# ArduinoGardener_1_0.net
KiCad netlist of a schematic drawn in EAGLE
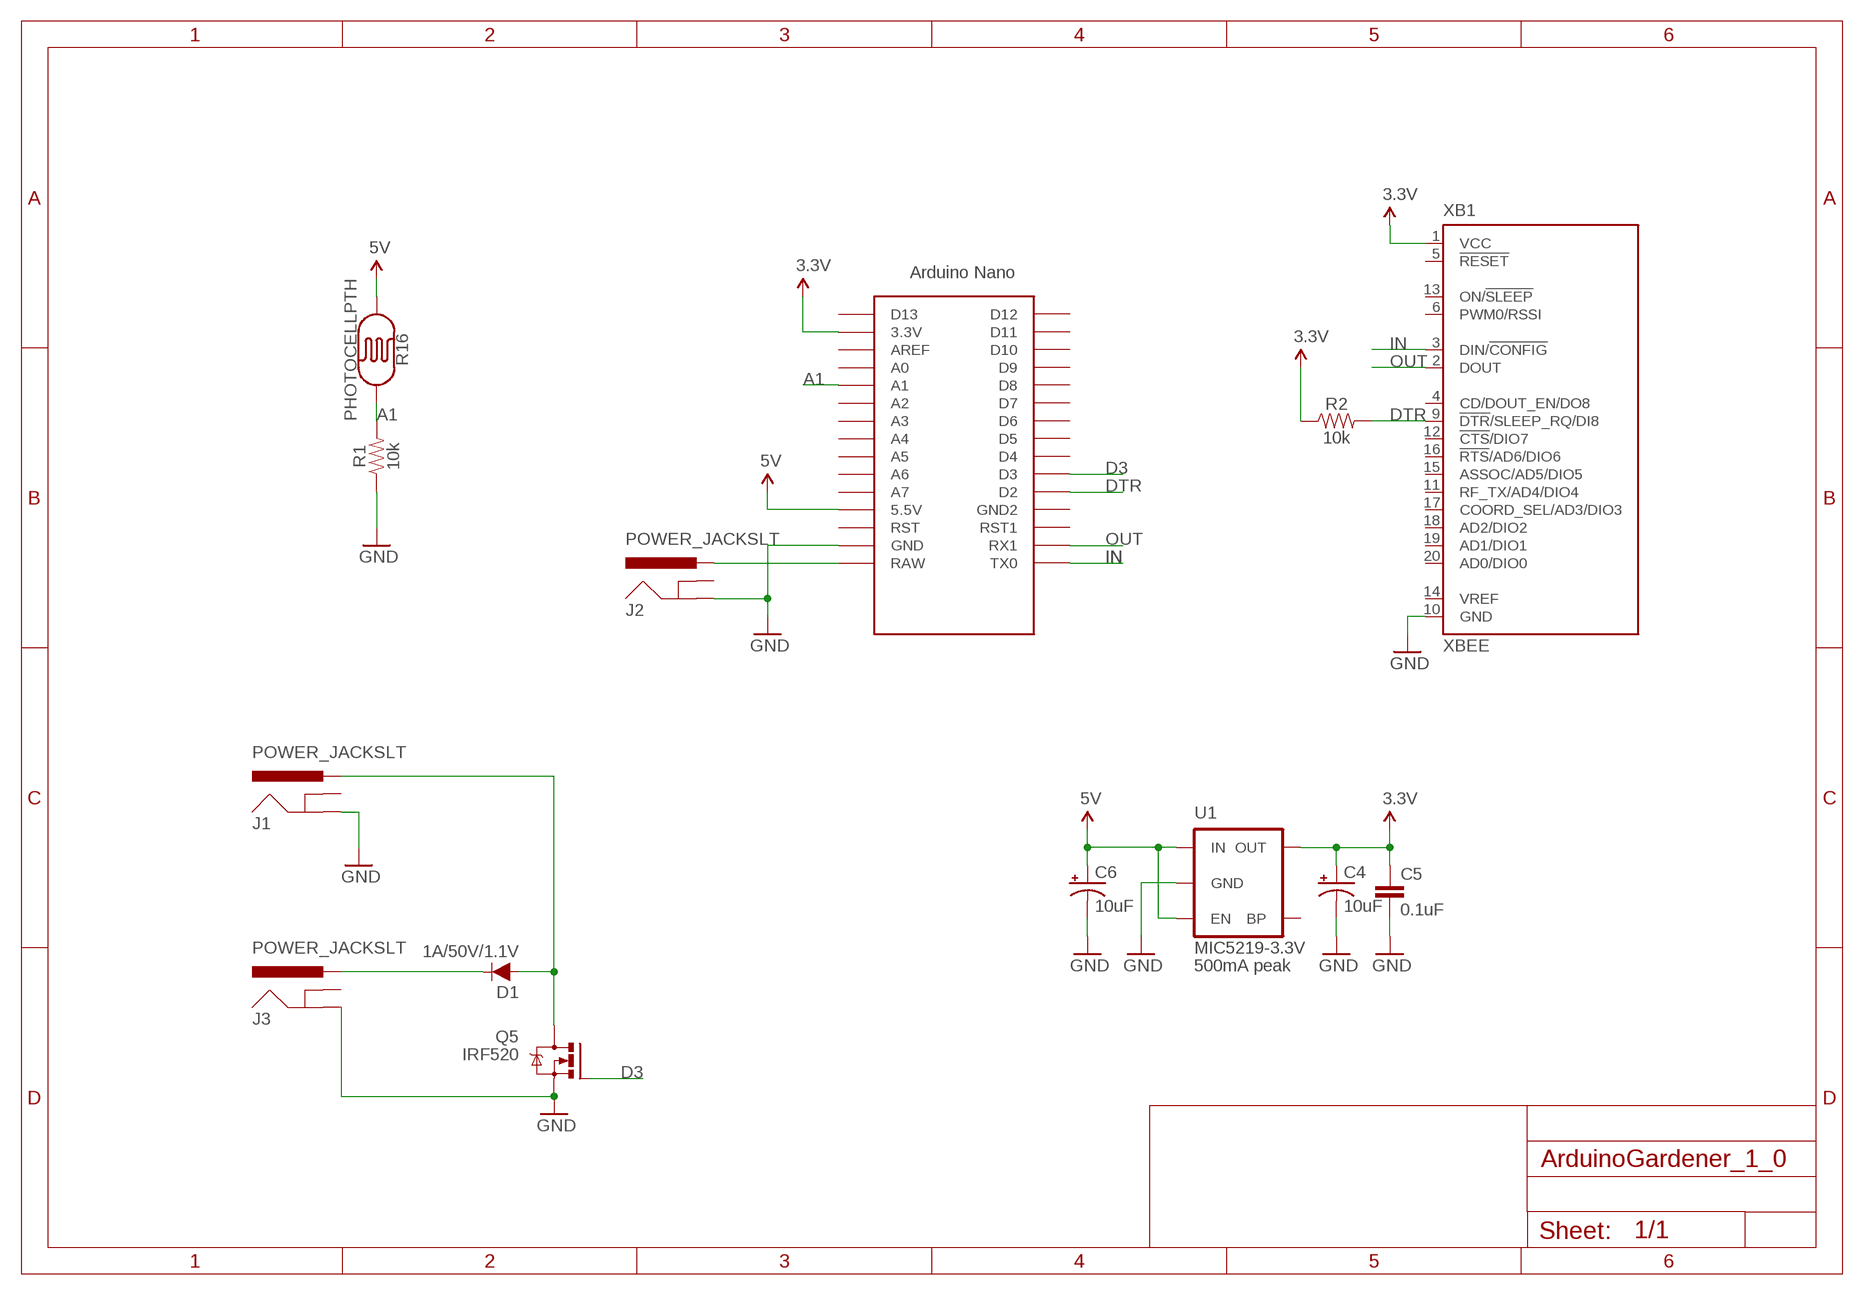
[diagram p0: schematic, sheet 1]

(export (version "E")
  (design (tool "Eeschema 10.0.6"))
  (components
    (comp (ref "C4")
      (value "10uF")
      (footprint "eagle-import:EIA3216")
      (libsource (lib "eagle-import") (part "CAP_POL1206"))
    )
    (comp (ref "C5")
      (value "0.1uF")
      (footprint "eagle-import:0402-CAP")
      (libsource (lib "eagle-import") (part "CAP0402-CAP"))
    )
    (comp (ref "C6")
      (value "10uF")
      (footprint "eagle-import:EIA3216")
      (libsource (lib "eagle-import") (part "CAP_POL1206"))
    )
    (comp (ref "D1")
      (value "1A/50V/1.1V")
      (footprint "eagle-import:DIODE-1N4001")
      (libsource (lib "eagle-import") (part "DIODE-PTH"))
    )
    (comp (ref "J1")
      (value "POWER_JACKSLT")
      (footprint "eagle-import:POWER_JACK_SLOT")
      (libsource (lib "eagle-import") (part "POWER_JACKSLT"))
    )
    (comp (ref "J2")
      (value "POWER_JACKSLT")
      (footprint "eagle-import:POWER_JACK_SLOT")
      (libsource (lib "eagle-import") (part "POWER_JACKSLT"))
    )
    (comp (ref "J3")
      (value "POWER_JACKSLT")
      (footprint "eagle-import:POWER_JACK_SLOT")
      (libsource (lib "eagle-import") (part "POWER_JACKSLT"))
    )
    (comp (ref "Q5")
      (value "IRF520")
      (footprint "eagle-import:TO220BV")
      (libsource (lib "eagle-import") (part "IRF520"))
    )
    (comp (ref "R1")
      (value "10k")
      (footprint "eagle-import:AXIAL-0.3")
      (libsource (lib "eagle-import") (part "10KOHM-HORIZ-1/4W-5%"))
    )
    (comp (ref "R2")
      (value "10k")
      (footprint "eagle-import:AXIAL-0.3")
      (libsource (lib "eagle-import") (part "10KOHM-HORIZ-1/4W-5%"))
    )
    (comp (ref "R16")
      (value "PHOTOCELLPTH")
      (footprint "eagle-import:PHOTOCELL")
      (libsource (lib "eagle-import") (part "PHOTOCELLPTH"))
    )
    (comp (ref "U$1")
      (value "NANO")
      (footprint "eagle-import:NANO")
      (libsource (lib "eagle-import") (part "NANO"))
    )
    (comp (ref "U1")
      (value "V_REG_LDOSMD")
      (footprint "eagle-import:SOT23-5")
      (libsource (lib "eagle-import") (part "V_REG_LDOSMD"))
    )
    (comp (ref "XB1")
      (value "XBEE")
      (footprint "eagle-import:XBEE")
      (fields (field (name "MPN") "XBP24-Z7UIT-004"))
      (libsource (lib "eagle-import") (part "XBEE"))
    )
  )
  (nets
    (net (code "1") (name "/A1") (class "Default")
      (node (ref "R1") (pin "P$2") (pinfunction "2_P$2") (pintype "passive"))
      (node (ref "R16") (pin "2") (pinfunction "P$2_2") (pintype "bidirectional"))
      (node (ref "U$1") (pin "A1") (pinfunction "A1_A1") (pintype "bidirectional"))
    )
    (net (code "2") (name "/D3") (class "Default")
      (node (ref "Q5") (pin "G") (pinfunction "G_G") (pintype "passive"))
      (node (ref "U$1") (pin "D3") (pinfunction "D3_D3") (pintype "bidirectional"))
    )
    (net (code "3") (name "/DTR") (class "Default")
      (node (ref "R2") (pin "P$2") (pinfunction "2_P$2") (pintype "passive"))
      (node (ref "U$1") (pin "D2") (pinfunction "D2_D2") (pintype "bidirectional"))
      (node (ref "XB1") (pin "9") (pinfunction "~{DTR}/SLEEP_RQ/DI8_9") (pintype "bidirectional"))
    )
    (net (code "4") (name "/IN") (class "Default")
      (node (ref "U$1") (pin "TX0") (pinfunction "TX0_TX0") (pintype "bidirectional"))
      (node (ref "XB1") (pin "3") (pinfunction "DIN/~{CONFIG}_3") (pintype "input"))
    )
    (net (code "5") (name "/OUT") (class "Default")
      (node (ref "U$1") (pin "RX1") (pinfunction "RX1_RX1") (pintype "bidirectional"))
      (node (ref "XB1") (pin "2") (pinfunction "DOUT_2") (pintype "output"))
    )
    (net (code "6") (name "3.3V") (class "Default")
      (node (ref "C4") (pin "A") (pinfunction "+_A") (pintype "passive"))
      (node (ref "C5") (pin "1") (pinfunction "1_1") (pintype "passive"))
      (node (ref "R2") (pin "P$1") (pinfunction "1_P$1") (pintype "passive"))
      (node (ref "U$1") (pin "3.3V") (pinfunction "3.3V_3.3V") (pintype "bidirectional"))
      (node (ref "U1") (pin "5") (pinfunction "OUT_5") (pintype "passive"))
      (node (ref "XB1") (pin "1") (pinfunction "VCC_1") (pintype "power_in"))
    )
    (net (code "7") (name "5V") (class "Default")
      (node (ref "C6") (pin "A") (pinfunction "+_A") (pintype "passive"))
      (node (ref "R16") (pin "1") (pinfunction "P$1_1") (pintype "bidirectional"))
      (node (ref "U$1") (pin "5V") (pinfunction "5.5V_5V") (pintype "bidirectional"))
      (node (ref "U1") (pin "1") (pinfunction "IN_1") (pintype "input"))
      (node (ref "U1") (pin "3") (pinfunction "EN_3") (pintype "input"))
    )
    (net (code "8") (name "GND") (class "Default")
      (node (ref "C4") (pin "C") (pinfunction "-_C") (pintype "passive"))
      (node (ref "C5") (pin "2") (pinfunction "2_2") (pintype "passive"))
      (node (ref "C6") (pin "C") (pinfunction "-_C") (pintype "passive"))
      (node (ref "J1") (pin "GND@2") (pinfunction "GND_GND@2") (pintype "bidirectional"))
      (node (ref "J2") (pin "GND@2") (pinfunction "GND_GND@2") (pintype "bidirectional"))
      (node (ref "J3") (pin "GND@2") (pinfunction "GND_GND@2") (pintype "bidirectional"))
      (node (ref "Q5") (pin "S") (pinfunction "S_S") (pintype "passive"))
      (node (ref "R1") (pin "P$1") (pinfunction "1_P$1") (pintype "passive"))
      (node (ref "U$1") (pin "GND") (pinfunction "GND_GND") (pintype "bidirectional"))
      (node (ref "U1") (pin "2") (pinfunction "GND_2") (pintype "input"))
      (node (ref "XB1") (pin "10") (pinfunction "GND_10") (pintype "power_in"))
    )
    (net (code "9") (name "Net-(D1-PadA)") (class "Default")
      (node (ref "D1") (pin "A") (pinfunction "A_A") (pintype "passive"))
      (node (ref "J1") (pin "PWR") (pinfunction "PWR_PWR") (pintype "bidirectional"))
      (node (ref "Q5") (pin "D") (pinfunction "D_D") (pintype "passive"))
    )
    (net (code "10") (name "Net-(D1-PadC)") (class "Default")
      (node (ref "D1") (pin "C") (pinfunction "C_C") (pintype "passive"))
      (node (ref "J3") (pin "PWR") (pinfunction "PWR_PWR") (pintype "bidirectional"))
    )
    (net (code "11") (name "Net-(J2-PadPWR)") (class "Default")
      (node (ref "J2") (pin "PWR") (pinfunction "PWR_PWR") (pintype "bidirectional"))
      (node (ref "U$1") (pin "RAW") (pinfunction "RAW_RAW") (pintype "bidirectional"))
    )
    (net (code "12") (name "unconnected-(J1-GNDBREAK-PadGND@1)") (class "Default")
      (node (ref "J1") (pin "GND@1") (pinfunction "GNDBREAK_GND@1") (pintype "bidirectional"))
    )
    (net (code "13") (name "unconnected-(J2-GNDBREAK-PadGND@1)") (class "Default")
      (node (ref "J2") (pin "GND@1") (pinfunction "GNDBREAK_GND@1") (pintype "bidirectional"))
    )
    (net (code "14") (name "unconnected-(J3-GNDBREAK-PadGND@1)") (class "Default")
      (node (ref "J3") (pin "GND@1") (pinfunction "GNDBREAK_GND@1") (pintype "bidirectional"))
    )
    (net (code "15") (name "unconnected-(U$1-GND2-PadGND1)") (class "Default")
      (node (ref "U$1") (pin "GND1") (pinfunction "GND2_GND1") (pintype "bidirectional"))
    )
    (net (code "16") (name "unconnected-(U$1-PadA0)") (class "Default")
      (node (ref "U$1") (pin "A0") (pinfunction "A0_A0") (pintype "bidirectional"))
    )
    (net (code "17") (name "unconnected-(U$1-PadA2)") (class "Default")
      (node (ref "U$1") (pin "A2") (pinfunction "A2_A2") (pintype "bidirectional"))
    )
    (net (code "18") (name "unconnected-(U$1-PadA3)") (class "Default")
      (node (ref "U$1") (pin "A3") (pinfunction "A3_A3") (pintype "bidirectional"))
    )
    (net (code "19") (name "unconnected-(U$1-PadA4)") (class "Default")
      (node (ref "U$1") (pin "A4") (pinfunction "A4_A4") (pintype "bidirectional"))
    )
    (net (code "20") (name "unconnected-(U$1-PadA5)") (class "Default")
      (node (ref "U$1") (pin "A5") (pinfunction "A5_A5") (pintype "bidirectional"))
    )
    (net (code "21") (name "unconnected-(U$1-PadA6)") (class "Default")
      (node (ref "U$1") (pin "A6") (pinfunction "A6_A6") (pintype "bidirectional"))
    )
    (net (code "22") (name "unconnected-(U$1-PadA7)") (class "Default")
      (node (ref "U$1") (pin "A7") (pinfunction "A7_A7") (pintype "bidirectional"))
    )
    (net (code "23") (name "unconnected-(U$1-PadAREF)") (class "Default")
      (node (ref "U$1") (pin "AREF") (pinfunction "AREF_AREF") (pintype "bidirectional"))
    )
    (net (code "24") (name "unconnected-(U$1-PadD4)") (class "Default")
      (node (ref "U$1") (pin "D4") (pinfunction "D4_D4") (pintype "bidirectional"))
    )
    (net (code "25") (name "unconnected-(U$1-PadD5)") (class "Default")
      (node (ref "U$1") (pin "D5") (pinfunction "D5_D5") (pintype "bidirectional"))
    )
    (net (code "26") (name "unconnected-(U$1-PadD6)") (class "Default")
      (node (ref "U$1") (pin "D6") (pinfunction "D6_D6") (pintype "bidirectional"))
    )
    (net (code "27") (name "unconnected-(U$1-PadD7)") (class "Default")
      (node (ref "U$1") (pin "D7") (pinfunction "D7_D7") (pintype "bidirectional"))
    )
    (net (code "28") (name "unconnected-(U$1-PadD8)") (class "Default")
      (node (ref "U$1") (pin "D8") (pinfunction "D8_D8") (pintype "bidirectional"))
    )
    (net (code "29") (name "unconnected-(U$1-PadD9)") (class "Default")
      (node (ref "U$1") (pin "D9") (pinfunction "D9_D9") (pintype "bidirectional"))
    )
    (net (code "30") (name "unconnected-(U$1-PadD10)") (class "Default")
      (node (ref "U$1") (pin "D10") (pinfunction "D10_D10") (pintype "bidirectional"))
    )
    (net (code "31") (name "unconnected-(U$1-PadD11)") (class "Default")
      (node (ref "U$1") (pin "D11") (pinfunction "D11_D11") (pintype "bidirectional"))
    )
    (net (code "32") (name "unconnected-(U$1-PadD12)") (class "Default")
      (node (ref "U$1") (pin "D12") (pinfunction "D12_D12") (pintype "bidirectional"))
    )
    (net (code "33") (name "unconnected-(U$1-PadD13)") (class "Default")
      (node (ref "U$1") (pin "D13") (pinfunction "D13_D13") (pintype "bidirectional"))
    )
    (net (code "34") (name "unconnected-(U$1-PadICSP1)") (class "Default")
      (node (ref "U$1") (pin "ICSP1") (pinfunction "ICSP1_ICSP1") (pintype "bidirectional"))
    )
    (net (code "35") (name "unconnected-(U$1-PadICSP2)") (class "Default")
      (node (ref "U$1") (pin "ICSP2") (pinfunction "ICSP2_ICSP2") (pintype "bidirectional"))
    )
    (net (code "36") (name "unconnected-(U$1-PadICSP3)") (class "Default")
      (node (ref "U$1") (pin "ICSP3") (pinfunction "ICSP3_ICSP3") (pintype "bidirectional"))
    )
    (net (code "37") (name "unconnected-(U$1-PadICSP4)") (class "Default")
      (node (ref "U$1") (pin "ICSP4") (pinfunction "ICSP4_ICSP4") (pintype "bidirectional"))
    )
    (net (code "38") (name "unconnected-(U$1-PadICSP5)") (class "Default")
      (node (ref "U$1") (pin "ICSP5") (pinfunction "ICSP5_ICSP5") (pintype "bidirectional"))
    )
    (net (code "39") (name "unconnected-(U$1-PadICSP6)") (class "Default")
      (node (ref "U$1") (pin "ICSP6") (pinfunction "ICSP6_ICSP6") (pintype "bidirectional"))
    )
    (net (code "40") (name "unconnected-(U$1-PadRST)") (class "Default")
      (node (ref "U$1") (pin "RST") (pinfunction "RST_RST") (pintype "bidirectional"))
    )
    (net (code "41") (name "unconnected-(U$1-PadRST1)") (class "Default")
      (node (ref "U$1") (pin "RST1") (pinfunction "RST1_RST1") (pintype "bidirectional"))
    )
    (net (code "42") (name "unconnected-(U1-BP-Pad4)") (class "Default")
      (node (ref "U1") (pin "4") (pinfunction "BP_4") (pintype "input"))
    )
    (net (code "43") (name "unconnected-(XB1-AD0{slash}DIO0-Pad20)") (class "Default")
      (node (ref "XB1") (pin "20") (pinfunction "AD0/DIO0_20") (pintype "bidirectional"))
    )
    (net (code "44") (name "unconnected-(XB1-AD1{slash}DIO1-Pad19)") (class "Default")
      (node (ref "XB1") (pin "19") (pinfunction "AD1/DIO1_19") (pintype "bidirectional"))
    )
    (net (code "45") (name "unconnected-(XB1-AD2{slash}DIO2-Pad18)") (class "Default")
      (node (ref "XB1") (pin "18") (pinfunction "AD2/DIO2_18") (pintype "bidirectional"))
    )
    (net (code "46") (name "unconnected-(XB1-ASSOC{slash}AD5{slash}DIO5-Pad15)") (class "Default")
      (node (ref "XB1") (pin "15") (pinfunction "ASSOC/AD5/DIO5_15") (pintype "bidirectional"))
    )
    (net (code "47") (name "unconnected-(XB1-CD{slash}DOUT_EN{slash}DO8-Pad4)") (class "Default")
      (node (ref "XB1") (pin "4") (pinfunction "CD/DOUT_EN/DO8_4") (pintype "output"))
    )
    (net (code "48") (name "unconnected-(XB1-COORD_SEL{slash}AD3{slash}DIO3-Pad17)") (class "Default")
      (node (ref "XB1") (pin "17") (pinfunction "COORD_SEL/AD3/DIO3_17") (pintype "bidirectional"))
    )
    (net (code "49") (name "unconnected-(XB1-ON{slash}~{SLEEP}-Pad13)") (class "Default")
      (node (ref "XB1") (pin "13") (pinfunction "ON/~{SLEEP}_13") (pintype "output"))
    )
    (net (code "50") (name "unconnected-(XB1-PWM0{slash}RSSI-Pad6)") (class "Default")
      (node (ref "XB1") (pin "6") (pinfunction "PWM0/RSSI_6") (pintype "output"))
    )
    (net (code "51") (name "unconnected-(XB1-RF_TX{slash}AD4{slash}DIO4-Pad11)") (class "Default")
      (node (ref "XB1") (pin "11") (pinfunction "RF_TX/AD4/DIO4_11") (pintype "bidirectional"))
    )
    (net (code "52") (name "unconnected-(XB1-VREF-Pad14)") (class "Default")
      (node (ref "XB1") (pin "14") (pinfunction "VREF_14") (pintype "input"))
    )
    (net (code "53") (name "unconnected-(XB1-~{CTS}{slash}DIO7-Pad12)") (class "Default")
      (node (ref "XB1") (pin "12") (pinfunction "~{CTS}/DIO7_12") (pintype "bidirectional"))
    )
    (net (code "54") (name "unconnected-(XB1-~{RESET}-Pad5)") (class "Default")
      (node (ref "XB1") (pin "5") (pinfunction "~{RESET}_5") (pintype "input"))
    )
    (net (code "55") (name "unconnected-(XB1-~{RTS}{slash}AD6{slash}DIO6-Pad16)") (class "Default")
      (node (ref "XB1") (pin "16") (pinfunction "~{RTS}/AD6/DIO6_16") (pintype "bidirectional"))
    )
  )
)
